# 001-0001_Christmas_Ornament_Battery_Char.net
KiCad netlist of a schematic drawn in Altium Designer
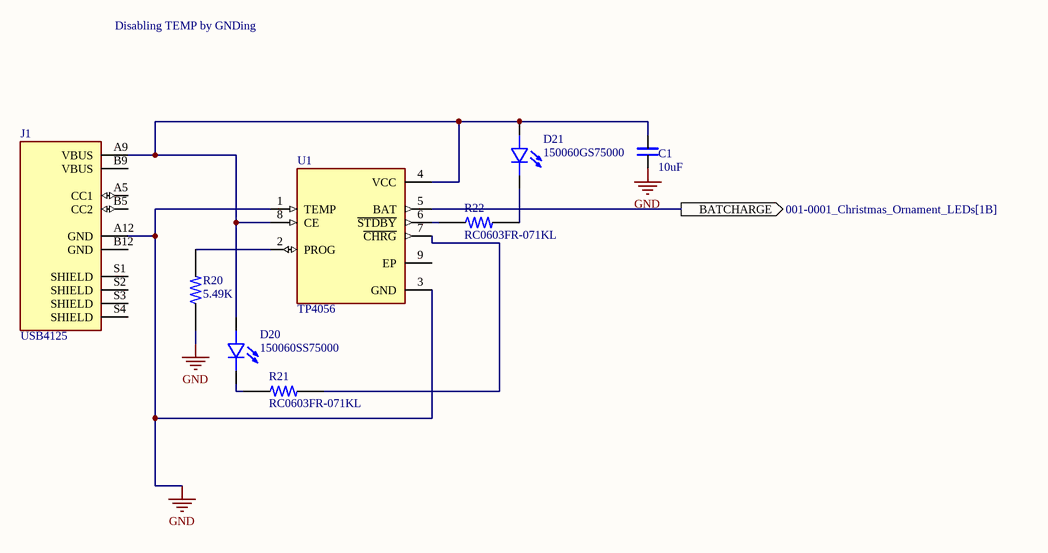
[diagram p0: 001-0001_Christmas_Ornament_Battery_Charging.SchDoc]

(export (version "E")
  (design (tool "Eeschema 10.0.6"))
  (components
    (comp (ref "C1")
      (value "10uF")
      (footprint "EMK107BC6106MA-T")
      (description "CAP CER 10UF 16V X6S 0603")
      (fields (field (name "MP") "EMK107BC6106MA-T"))
      (libsource (lib "default") (part "EMK107BC6106MA-T"))
    )
    (comp (ref "D20")
      (value "150060SS75000")
      (footprint "LED_150060SS75000")
      (fields (field (name "MF") "{'manufacturer': u'Wurth Electronics'}"))
      (libsource (lib "default") (part "150060SS75000"))
    )
    (comp (ref "D21")
      (value "150060GS75000")
      (footprint "LEDC1608X80N")
      (description "Green 520nm LED Indication - Discrete 3.2V 0603 (1608 Metric)")
      (fields (field (name "MF") "Wurth Electronics"))
      (libsource (lib "default") (part "150060GS75000"))
    )
    (comp (ref "J1")
      (value "USB4125")
      (footprint "USB4125-GF-A-0190")
      (description "Type C Receptacle, Horizontal, SMT, For Power Charging Only")
      (fields (field (name "MF") "Global Connector Technology") (field (name "MP") "USB4125-GF-A-0190"))
      (libsource (lib "default") (part "USB4125-GF-A-0190"))
    )
    (comp (ref "R20")
      (value "5.49K")
      (footprint "default:ERJ-PA3F51R0V")
      (description "RES SMD 5.49K OHM 1% 1/10W 0603")
      (fields (field (name "MP") "ERJPA3F51R0V"))
      (libsource (lib "default") (part "ERJ-3EKF5491V"))
    )
    (comp (ref "R21")
      (value "RC0603FR-071KL")
      (footprint "RESC1607X60N")
      (description "1 kOhms Â±1% 0.1W, 1/10W Chip Resistor 0603 (1608 Metric) Moisture Resistant Thick Film")
      (fields (field (name "MF") "Yageo"))
      (libsource (lib "default") (part "RC0603FR-071KL"))
    )
    (comp (ref "R22")
      (value "RC0603FR-071KL")
      (footprint "RESC1607X60N")
      (description "1 kOhms Â±1% 0.1W, 1/10W Chip Resistor 0603 (1608 Metric) Moisture Resistant Thick Film")
      (fields (field (name "MF") "Yageo"))
      (libsource (lib "default") (part "RC0603FR-071KL"))
    )
    (comp (ref "U1")
      (value "TP4056")
      (footprint "TP4056")
      (description "Complete single cell Li-Ion battery with a constant current / constant voltage linear charger")
      (fields (field (name "MF") "NanJing Top Power ASIC Corp."))
      (libsource (lib "default") (part "TP4056"))
    )
  )
  (nets
    (net (code "1") (name "/BATCHARGE") (class "Default")
      (node (ref "U1") (pin "5") (pinfunction "BAT_5") (pintype "output"))
    )
    (net (code "2") (name "GND") (class "Default")
      (node (ref "C1") (pin "1") (pinfunction "1_1") (pintype "passive"))
      (node (ref "J1") (pin "A12") (pinfunction "GND_A12") (pintype "power_in"))
      (node (ref "R20") (pin "1") (pinfunction "1_1") (pintype "passive"))
      (node (ref "U1") (pin "1") (pinfunction "TEMP_1") (pintype "input"))
      (node (ref "U1") (pin "3") (pinfunction "GND_3") (pintype "power_in"))
    )
    (net (code "3") (name "Net-(D20-PadC)") (class "Default")
      (node (ref "D20") (pin "C") (pinfunction "C_C") (pintype "passive"))
      (node (ref "R21") (pin "1") (pinfunction "1_1") (pintype "passive"))
    )
    (net (code "4") (name "Net-(D21-PadC)") (class "Default")
      (node (ref "D21") (pin "C") (pinfunction "C_C") (pintype "passive"))
      (node (ref "R22") (pin "2") (pinfunction "2_2") (pintype "passive"))
    )
    (net (code "5") (name "Net-(U1-CE)") (class "Default")
      (node (ref "C1") (pin "2") (pinfunction "2_2") (pintype "passive"))
      (node (ref "D20") (pin "A") (pinfunction "A_A") (pintype "passive"))
      (node (ref "D21") (pin "A") (pinfunction "A_A") (pintype "passive"))
      (node (ref "J1") (pin "A9") (pinfunction "VBUS_A9") (pintype "power_in"))
      (node (ref "U1") (pin "4") (pinfunction "VCC_4") (pintype "power_in"))
      (node (ref "U1") (pin "8") (pinfunction "CE_8") (pintype "input"))
    )
    (net (code "6") (name "Net-(U1-PROG)") (class "Default")
      (node (ref "R20") (pin "2") (pinfunction "2_2") (pintype "passive"))
      (node (ref "U1") (pin "2") (pinfunction "PROG_2") (pintype "bidirectional"))
    )
    (net (code "7") (name "Net-(U1-~{CHRG})") (class "Default")
      (node (ref "R21") (pin "2") (pinfunction "2_2") (pintype "passive"))
      (node (ref "U1") (pin "7") (pinfunction "~{CHRG}_7") (pintype "output"))
    )
    (net (code "8") (name "Net-(U1-~{STDBY})") (class "Default")
      (node (ref "R22") (pin "1") (pinfunction "1_1") (pintype "passive"))
      (node (ref "U1") (pin "6") (pinfunction "~{STDBY}_6") (pintype "output"))
    )
    (net (code "9") (name "unconnected-(J1-CC1-PadA5)") (class "Default")
      (node (ref "J1") (pin "A5") (pinfunction "CC1_A5") (pintype "bidirectional"))
    )
    (net (code "10") (name "unconnected-(J1-CC2-PadB5)") (class "Default")
      (node (ref "J1") (pin "B5") (pinfunction "CC2_B5") (pintype "bidirectional"))
    )
    (net (code "11") (name "unconnected-(J1-GND-PadB12)") (class "Default")
      (node (ref "J1") (pin "B12") (pinfunction "GND_B12") (pintype "power_in"))
    )
    (net (code "12") (name "unconnected-(J1-SHIELD-PadS1)") (class "Default")
      (node (ref "J1") (pin "S1") (pinfunction "SHIELD_S1") (pintype "passive"))
    )
    (net (code "13") (name "unconnected-(J1-SHIELD-PadS2)") (class "Default")
      (node (ref "J1") (pin "S2") (pinfunction "SHIELD_S2") (pintype "passive"))
    )
    (net (code "14") (name "unconnected-(J1-SHIELD-PadS3)") (class "Default")
      (node (ref "J1") (pin "S3") (pinfunction "SHIELD_S3") (pintype "passive"))
    )
    (net (code "15") (name "unconnected-(J1-SHIELD-PadS4)") (class "Default")
      (node (ref "J1") (pin "S4") (pinfunction "SHIELD_S4") (pintype "passive"))
    )
    (net (code "16") (name "unconnected-(J1-VBUS-PadB9)") (class "Default")
      (node (ref "J1") (pin "B9") (pinfunction "VBUS_B9") (pintype "power_in"))
    )
    (net (code "17") (name "unconnected-(U1-EP-Pad9)") (class "Default")
      (node (ref "U1") (pin "9") (pinfunction "EP_9") (pintype "passive"))
    )
  )
)
